# Lockbox_Schematic_V0_4.net
KiCad netlist of a schematic drawn in Altium Designer
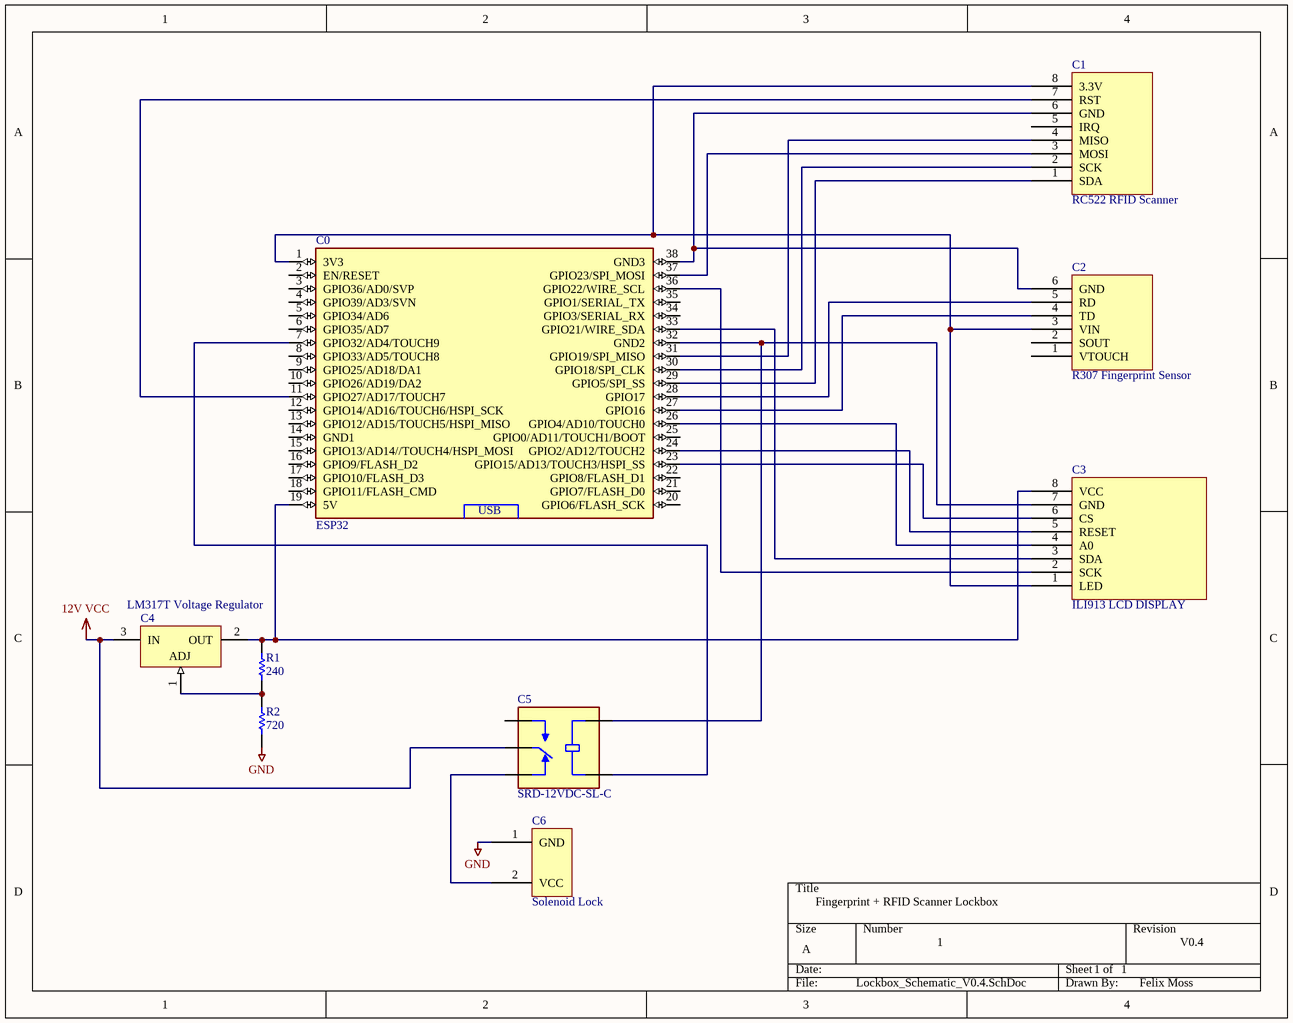
[diagram p0: Lockbox_Schematic_V0.4.SchDoc]

(export (version "E")
  (design (tool "Eeschema 10.0.6"))
  (components
    (comp (ref "C0")
      (value "ESP32")
      (footprint "ESP32-DEVKITC")
      (fields (field (name "MF") "Espressif Systems") (field (name "MP") "ESP32-DevKitC"))
      (libsource (lib "ESP32-DEVKITC") (part "ESP32-DEVKITC"))
    )
    (comp (ref "C1")
      (value "RC522 RFID Scanner")
      (description "RFID Scanner")
      (libsource (lib "Fingerprint_Mechanism_Library") (part "RFID-RC522"))
    )
    (comp (ref "C2")
      (value "R307 Fingerprint Sensor")
      (description "Fingerprint Sensor Powered by AS608")
      (libsource (lib "Fingerprint_Mechanism_Library") (part "Fingerprint Sensor"))
    )
    (comp (ref "C3")
      (value "ILI913 LCD DISPLAY")
      (description "LCD-1217")
      (libsource (lib "Fingerprint_Mechanism_Library") (part "LCD TFT DISPLAY"))
    )
    (comp (ref "C4")
      (value "LM317T Voltage Regulator")
      (footprint "TO-220")
      (description "1.5A, 1.2V to 37V Adjustable Voltage Regulator, 3-Pin TO-220")
      (libsource (lib "Altium Content Vault") (part "PM-REG-117-SIL3"))
    )
    (comp (ref "C5")
      (value "SRD-12VDC-SL-C")
      (footprint "RELAY_SRD-12VDC-SL-C")
      (description "General Purpose Non Latching 12VDC SPDT Through Hole Relays RoHS")
      (libsource (lib "SRD-12VDC-SL-C") (part "SRD-12VDC-SL-C"))
    )
    (comp (ref "C6")
      (value "Solenoid Lock")
      (description "12V 1.1A Solenoid Lock")
      (libsource (lib "Fingerprint_Mechanism_Library") (part "Solenoid Lock"))
    )
    (comp (ref "R1")
      (value "240")
      (description "Resistor")
      (libsource (lib "Simulation Generic Components") (part "Resistor"))
    )
    (comp (ref "R2")
      (value "720")
      (description "Resistor")
      (libsource (lib "Simulation Generic Components") (part "Resistor"))
    )
  )
  (nets
    (net (code "1") (name "12V VCC") (class "Default")
      (node (ref "C4") (pin "3") (pinfunction "IN_3") (pintype "power_in"))
      (node (ref "C5") (pin "COM") (pinfunction "COM_COM") (pintype "passive"))
    )
    (net (code "2") (name "GND") (class "Default")
      (node (ref "C6") (pin "1") (pinfunction "GND_1") (pintype "passive"))
      (node (ref "R2") (pin "1") (pinfunction "1_1") (pintype "passive"))
    )
    (net (code "3") (name "Net-(C0-3V3)") (class "Default")
      (node (ref "C0") (pin "1") (pinfunction "3V3_1") (pintype "bidirectional"))
      (node (ref "C1") (pin "8") (pinfunction "3.3V_8") (pintype "passive"))
      (node (ref "C2") (pin "3") (pinfunction "VIN_3") (pintype "passive"))
      (node (ref "C3") (pin "1") (pinfunction "LED_1") (pintype "passive"))
    )
    (net (code "4") (name "Net-(C0-5V)") (class "Default")
      (node (ref "C0") (pin "19") (pinfunction "5V_19") (pintype "bidirectional"))
      (node (ref "C3") (pin "8") (pinfunction "VCC_8") (pintype "passive"))
      (node (ref "C4") (pin "2") (pinfunction "OUT_2") (pintype "power_in"))
      (node (ref "R1") (pin "1") (pinfunction "1_1") (pintype "passive"))
    )
    (net (code "5") (name "Net-(C0-GND2)") (class "Default")
      (node (ref "C0") (pin "32") (pinfunction "GND2_32") (pintype "bidirectional"))
      (node (ref "C3") (pin "7") (pinfunction "GND_7") (pintype "passive"))
      (node (ref "C5") (pin "COIL2") (pinfunction "COIL2_COIL2") (pintype "passive"))
    )
    (net (code "6") (name "Net-(C0-GND3)") (class "Default")
      (node (ref "C0") (pin "38") (pinfunction "GND3_38") (pintype "bidirectional"))
      (node (ref "C1") (pin "6") (pinfunction "GND_6") (pintype "passive"))
      (node (ref "C2") (pin "6") (pinfunction "GND_6") (pintype "passive"))
    )
    (net (code "7") (name "Net-(C0-GPIO2{slash}AD12{slash}TOUCH2)") (class "Default")
      (node (ref "C0") (pin "24") (pinfunction "GPIO2/AD12/TOUCH2_24") (pintype "bidirectional"))
      (node (ref "C3") (pin "5") (pinfunction "RESET_5") (pintype "passive"))
    )
    (net (code "8") (name "Net-(C0-GPIO4{slash}AD10{slash}TOUCH0)") (class "Default")
      (node (ref "C0") (pin "26") (pinfunction "GPIO4/AD10/TOUCH0_26") (pintype "bidirectional"))
      (node (ref "C3") (pin "4") (pinfunction "A0_4") (pintype "passive"))
    )
    (net (code "9") (name "Net-(C0-GPIO5{slash}SPI_SS)") (class "Default")
      (node (ref "C0") (pin "29") (pinfunction "GPIO5/SPI_SS_29") (pintype "bidirectional"))
      (node (ref "C1") (pin "1") (pinfunction "SDA_1") (pintype "passive"))
    )
    (net (code "10") (name "Net-(C0-GPIO15{slash}AD13{slash}TOUCH3{slash}HSPI_SS)") (class "Default")
      (node (ref "C0") (pin "23") (pinfunction "GPIO15/AD13/TOUCH3/HSPI_SS_23") (pintype "bidirectional"))
      (node (ref "C3") (pin "6") (pinfunction "CS_6") (pintype "passive"))
    )
    (net (code "11") (name "Net-(C0-GPIO16)") (class "Default")
      (node (ref "C0") (pin "27") (pinfunction "GPIO16_27") (pintype "bidirectional"))
      (node (ref "C2") (pin "4") (pinfunction "TD_4") (pintype "passive"))
    )
    (net (code "12") (name "Net-(C0-GPIO17)") (class "Default")
      (node (ref "C0") (pin "28") (pinfunction "GPIO17_28") (pintype "bidirectional"))
      (node (ref "C2") (pin "5") (pinfunction "RD_5") (pintype "passive"))
    )
    (net (code "13") (name "Net-(C0-GPIO18{slash}SPI_CLK)") (class "Default")
      (node (ref "C0") (pin "30") (pinfunction "GPIO18/SPI_CLK_30") (pintype "bidirectional"))
      (node (ref "C1") (pin "2") (pinfunction "SCK_2") (pintype "passive"))
    )
    (net (code "14") (name "Net-(C0-GPIO19{slash}SPI_MISO)") (class "Default")
      (node (ref "C0") (pin "31") (pinfunction "GPIO19/SPI_MISO_31") (pintype "bidirectional"))
      (node (ref "C1") (pin "4") (pinfunction "MISO_4") (pintype "passive"))
    )
    (net (code "15") (name "Net-(C0-GPIO21{slash}WIRE_SDA)") (class "Default")
      (node (ref "C0") (pin "33") (pinfunction "GPIO21/WIRE_SDA_33") (pintype "bidirectional"))
      (node (ref "C3") (pin "3") (pinfunction "SDA_3") (pintype "passive"))
    )
    (net (code "16") (name "Net-(C0-GPIO22{slash}WIRE_SCL)") (class "Default")
      (node (ref "C0") (pin "36") (pinfunction "GPIO22/WIRE_SCL_36") (pintype "bidirectional"))
      (node (ref "C3") (pin "2") (pinfunction "SCK_2") (pintype "passive"))
    )
    (net (code "17") (name "Net-(C0-GPIO23{slash}SPI_MOSI)") (class "Default")
      (node (ref "C0") (pin "37") (pinfunction "GPIO23/SPI_MOSI_37") (pintype "bidirectional"))
      (node (ref "C1") (pin "3") (pinfunction "MOSI_3") (pintype "passive"))
    )
    (net (code "18") (name "Net-(C0-GPIO27{slash}AD17{slash}TOUCH7)") (class "Default")
      (node (ref "C0") (pin "11") (pinfunction "GPIO27/AD17/TOUCH7_11") (pintype "bidirectional"))
      (node (ref "C1") (pin "7") (pinfunction "RST_7") (pintype "passive"))
    )
    (net (code "19") (name "Net-(C0-GPIO32{slash}AD4{slash}TOUCH9)") (class "Default")
      (node (ref "C0") (pin "7") (pinfunction "GPIO32/AD4/TOUCH9_7") (pintype "bidirectional"))
      (node (ref "C5") (pin "COIL1") (pinfunction "COIL1_COIL1") (pintype "passive"))
    )
    (net (code "20") (name "Net-(C4-ADJ)") (class "Default")
      (node (ref "C4") (pin "1") (pinfunction "ADJ_1") (pintype "input"))
      (node (ref "R1") (pin "2") (pinfunction "2_2") (pintype "passive"))
      (node (ref "R2") (pin "2") (pinfunction "2_2") (pintype "passive"))
    )
    (net (code "21") (name "Net-(C6-VCC)") (class "Default")
      (node (ref "C5") (pin "NC") (pinfunction "NC_NC") (pintype "passive"))
      (node (ref "C6") (pin "2") (pinfunction "VCC_2") (pintype "passive"))
    )
    (net (code "22") (name "unconnected-(C0-EN{slash}RESET-Pad2)") (class "Default")
      (node (ref "C0") (pin "2") (pinfunction "EN/RESET_2") (pintype "bidirectional"))
    )
    (net (code "23") (name "unconnected-(C0-GND1-Pad14)") (class "Default")
      (node (ref "C0") (pin "14") (pinfunction "GND1_14") (pintype "bidirectional"))
    )
    (net (code "24") (name "unconnected-(C0-GPIO0{slash}AD11{slash}TOUCH1{slash}BOOT-Pad25)") (class "Default")
      (node (ref "C0") (pin "25") (pinfunction "GPIO0/AD11/TOUCH1/BOOT_25") (pintype "bidirectional"))
    )
    (net (code "25") (name "unconnected-(C0-GPIO1{slash}SERIAL_TX-Pad35)") (class "Default")
      (node (ref "C0") (pin "35") (pinfunction "GPIO1/SERIAL_TX_35") (pintype "bidirectional"))
    )
    (net (code "26") (name "unconnected-(C0-GPIO3{slash}SERIAL_RX-Pad34)") (class "Default")
      (node (ref "C0") (pin "34") (pinfunction "GPIO3/SERIAL_RX_34") (pintype "bidirectional"))
    )
    (net (code "27") (name "unconnected-(C0-GPIO6{slash}FLASH_SCK-Pad20)") (class "Default")
      (node (ref "C0") (pin "20") (pinfunction "GPIO6/FLASH_SCK_20") (pintype "bidirectional"))
    )
    (net (code "28") (name "unconnected-(C0-GPIO7{slash}FLASH_D0-Pad21)") (class "Default")
      (node (ref "C0") (pin "21") (pinfunction "GPIO7/FLASH_D0_21") (pintype "bidirectional"))
    )
    (net (code "29") (name "unconnected-(C0-GPIO8{slash}FLASH_D1-Pad22)") (class "Default")
      (node (ref "C0") (pin "22") (pinfunction "GPIO8/FLASH_D1_22") (pintype "bidirectional"))
    )
    (net (code "30") (name "unconnected-(C0-GPIO9{slash}FLASH_D2-Pad16)") (class "Default")
      (node (ref "C0") (pin "16") (pinfunction "GPIO9/FLASH_D2_16") (pintype "bidirectional"))
    )
    (net (code "31") (name "unconnected-(C0-GPIO10{slash}FLASH_D3-Pad17)") (class "Default")
      (node (ref "C0") (pin "17") (pinfunction "GPIO10/FLASH_D3_17") (pintype "bidirectional"))
    )
    (net (code "32") (name "unconnected-(C0-GPIO11{slash}FLASH_CMD-Pad18)") (class "Default")
      (node (ref "C0") (pin "18") (pinfunction "GPIO11/FLASH_CMD_18") (pintype "bidirectional"))
    )
    (net (code "33") (name "unconnected-(C0-GPIO12{slash}AD15{slash}TOUCH5{slash}HSPI_MISO-Pad13)") (class "Default")
      (node (ref "C0") (pin "13") (pinfunction "GPIO12/AD15/TOUCH5/HSPI_MISO_13") (pintype "bidirectional"))
    )
    (net (code "34") (name "unconnected-(C0-GPIO13{slash}AD14{slash}{slash}TOUCH4{slash}HSPI_MOSI-Pad15)") (class "Default")
      (node (ref "C0") (pin "15") (pinfunction "GPIO13/AD14//TOUCH4/HSPI_MOSI_15") (pintype "bidirectional"))
    )
    (net (code "35") (name "unconnected-(C0-GPIO14{slash}AD16{slash}TOUCH6{slash}HSPI_SCK-Pad12)") (class "Default")
      (node (ref "C0") (pin "12") (pinfunction "GPIO14/AD16/TOUCH6/HSPI_SCK_12") (pintype "bidirectional"))
    )
    (net (code "36") (name "unconnected-(C0-GPIO25{slash}AD18{slash}DA1-Pad9)") (class "Default")
      (node (ref "C0") (pin "9") (pinfunction "GPIO25/AD18/DA1_9") (pintype "bidirectional"))
    )
    (net (code "37") (name "unconnected-(C0-GPIO26{slash}AD19{slash}DA2-Pad10)") (class "Default")
      (node (ref "C0") (pin "10") (pinfunction "GPIO26/AD19/DA2_10") (pintype "bidirectional"))
    )
    (net (code "38") (name "unconnected-(C0-GPIO33{slash}AD5{slash}TOUCH8-Pad8)") (class "Default")
      (node (ref "C0") (pin "8") (pinfunction "GPIO33/AD5/TOUCH8_8") (pintype "bidirectional"))
    )
    (net (code "39") (name "unconnected-(C0-GPIO34{slash}AD6-Pad5)") (class "Default")
      (node (ref "C0") (pin "5") (pinfunction "GPIO34/AD6_5") (pintype "bidirectional"))
    )
    (net (code "40") (name "unconnected-(C0-GPIO35{slash}AD7-Pad6)") (class "Default")
      (node (ref "C0") (pin "6") (pinfunction "GPIO35/AD7_6") (pintype "bidirectional"))
    )
    (net (code "41") (name "unconnected-(C0-GPIO36{slash}AD0{slash}SVP-Pad3)") (class "Default")
      (node (ref "C0") (pin "3") (pinfunction "GPIO36/AD0/SVP_3") (pintype "bidirectional"))
    )
    (net (code "42") (name "unconnected-(C0-GPIO39{slash}AD3{slash}SVN-Pad4)") (class "Default")
      (node (ref "C0") (pin "4") (pinfunction "GPIO39/AD3/SVN_4") (pintype "bidirectional"))
    )
    (net (code "43") (name "unconnected-(C1-IRQ-Pad5)") (class "Default")
      (node (ref "C1") (pin "5") (pinfunction "IRQ_5") (pintype "passive"))
    )
    (net (code "44") (name "unconnected-(C2-SOUT-Pad2)") (class "Default")
      (node (ref "C2") (pin "2") (pinfunction "SOUT_2") (pintype "passive"))
    )
    (net (code "45") (name "unconnected-(C2-VTOUCH-Pad1)") (class "Default")
      (node (ref "C2") (pin "1") (pinfunction "VTOUCH_1") (pintype "passive"))
    )
    (net (code "46") (name "unconnected-(C5-PadNO)") (class "Default")
      (node (ref "C5") (pin "NO") (pinfunction "NO_NO") (pintype "passive"))
    )
  )
)
